# ATtinyBoard_capBall.net
KiCad netlist of a schematic drawn in EAGLE
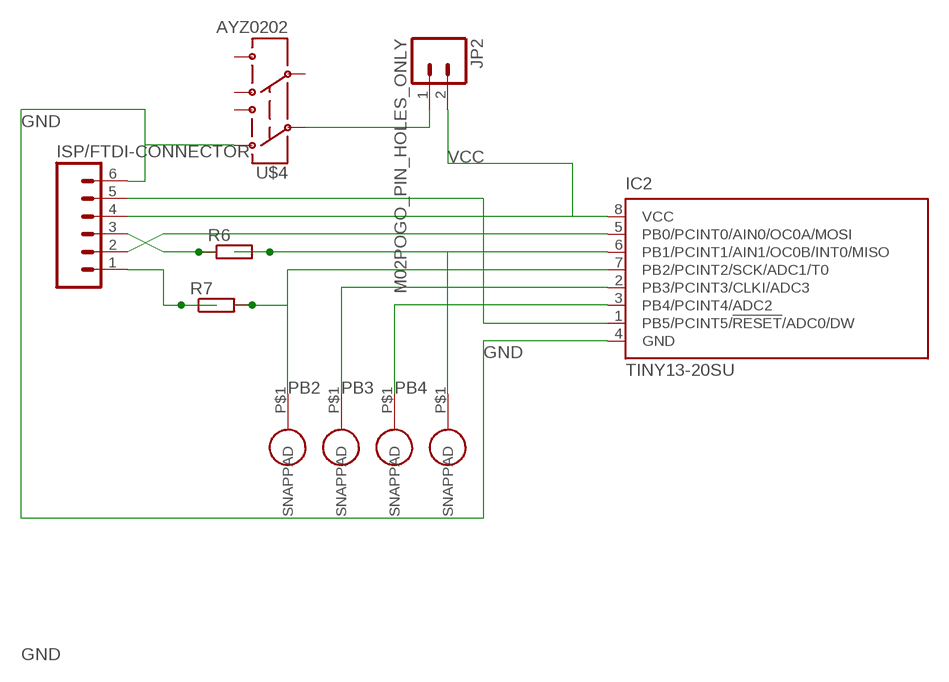
[diagram p0: schematic, sheet 1]

(export (version "E")
  (design (tool "Eeschema 10.0.6"))
  (components
    (comp (ref "IC2")
      (value "TINY13-20SU")
      (footprint "eagle-import:8S2")
      (fields (field (name "MPN") "ATTINY13-20SU"))
      (libsource (lib "eagle-import") (part "TINY13SU-20"))
    )
    (comp (ref "ISP/FTDI-CONNECTOR")
      (value "M06SMD")
      (footprint "eagle-import:1X06-SMD")
      (libsource (lib "eagle-import") (part "M06SMD"))
    )
    (comp (ref "JP2")
      (value "M02POGO_PIN_HOLES_ONLY")
      (footprint "eagle-import:1X02_PP_HOLES_ONLY")
      (libsource (lib "eagle-import") (part "M02POGO_PIN_HOLES_ONLY"))
    )
    (comp (ref "R6")
      (value "R-EU_R2012")
      (footprint "eagle-import:R2012")
      (libsource (lib "eagle-import") (part "R-EU_R2012"))
    )
    (comp (ref "R7")
      (value "R-EU_R2012")
      (footprint "eagle-import:R2012")
      (libsource (lib "eagle-import") (part "R-EU_R2012"))
    )
    (comp (ref "U$1")
      (value "SNAP-PAD_7MM_ROUND")
      (footprint "eagle-import:SNAP-PAD_7MM_RD")
      (libsource (lib "eagle-import") (part "SNAP-PAD_7MM_ROUND"))
    )
    (comp (ref "U$2")
      (value "SNAP-PAD_7MM_ROUND")
      (footprint "eagle-import:SNAP-PAD_7MM_RD")
      (libsource (lib "eagle-import") (part "SNAP-PAD_7MM_ROUND"))
    )
    (comp (ref "U$3")
      (value "SNAP-PAD_7MM_ROUND")
      (footprint "eagle-import:SNAP-PAD_7MM_RD")
      (libsource (lib "eagle-import") (part "SNAP-PAD_7MM_ROUND"))
    )
    (comp (ref "U$4")
      (value "AYZ0202")
      (footprint "eagle-import:AYZ0202")
      (libsource (lib "eagle-import") (part "AYZ0202"))
    )
    (comp (ref "U$6")
      (value "SNAP-PAD_7MM_ROUND")
      (footprint "eagle-import:SNAP-PAD_7MM_RD")
      (libsource (lib "eagle-import") (part "SNAP-PAD_7MM_ROUND"))
    )
  )
  (nets
    (net (code "1") (name "/GND") (class "Default")
      (node (ref "IC2") (pin "4") (pinfunction "GND_4") (pintype "power_in"))
      (node (ref "ISP/FTDI-CONNECTOR") (pin "6") (pinfunction "6_6") (pintype "passive"))
      (node (ref "U$4") (pin "3") (pinfunction "1_3") (pintype "bidirectional"))
    )
    (net (code "2") (name "/PB2") (class "Default")
      (node (ref "IC2") (pin "7") (pinfunction "PB2/PCINT2/SCK/ADC1/T0_7") (pintype "bidirectional"))
      (node (ref "R7") (pin "2") (pinfunction "2_2") (pintype "passive"))
      (node (ref "U$1") (pin "P$1") (pinfunction "SNAPPAD_P$1") (pintype "bidirectional"))
    )
    (net (code "3") (name "/PB3") (class "Default")
      (node (ref "IC2") (pin "2") (pinfunction "PB3/PCINT3/CLKI/ADC3_2") (pintype "bidirectional"))
      (node (ref "U$2") (pin "P$1") (pinfunction "SNAPPAD_P$1") (pintype "bidirectional"))
    )
    (net (code "4") (name "/PB4") (class "Default")
      (node (ref "IC2") (pin "3") (pinfunction "PB4/PCINT4/ADC2_3") (pintype "bidirectional"))
      (node (ref "U$3") (pin "P$1") (pinfunction "SNAPPAD_P$1") (pintype "bidirectional"))
    )
    (net (code "5") (name "/VCC") (class "Default")
      (node (ref "IC2") (pin "8") (pinfunction "VCC_8") (pintype "power_in"))
      (node (ref "ISP/FTDI-CONNECTOR") (pin "4") (pinfunction "4_4") (pintype "passive"))
      (node (ref "JP2") (pin "2") (pinfunction "2_2") (pintype "passive"))
    )
    (net (code "6") (name "Net-(IC2-PB0{slash}PCINT0{slash}AIN0{slash}OC0A{slash}MOSI)") (class "Default")
      (node (ref "IC2") (pin "5") (pinfunction "PB0/PCINT0/AIN0/OC0A/MOSI_5") (pintype "bidirectional"))
      (node (ref "ISP/FTDI-CONNECTOR") (pin "2") (pinfunction "2_2") (pintype "passive"))
    )
    (net (code "7") (name "Net-(IC2-PB1{slash}PCINT1{slash}AIN1{slash}OC0B{slash}INT0{slash}MISO)") (class "Default")
      (node (ref "IC2") (pin "6") (pinfunction "PB1/PCINT1/AIN1/OC0B/INT0/MISO_6") (pintype "bidirectional"))
      (node (ref "R6") (pin "2") (pinfunction "2_2") (pintype "passive"))
      (node (ref "U$6") (pin "P$1") (pinfunction "SNAPPAD_P$1") (pintype "bidirectional"))
    )
    (net (code "8") (name "Net-(IC2-PB5{slash}PCINT5{slash}~{RESET}{slash}ADC0{slash}DW)") (class "Default")
      (node (ref "IC2") (pin "1") (pinfunction "PB5/PCINT5/~{RESET}/ADC0/DW_1") (pintype "bidirectional"))
      (node (ref "ISP/FTDI-CONNECTOR") (pin "5") (pinfunction "5_5") (pintype "passive"))
    )
    (net (code "9") (name "Net-(ISP/FTDI-CONNECTOR-Pad1)") (class "Default")
      (node (ref "ISP/FTDI-CONNECTOR") (pin "1") (pinfunction "1_1") (pintype "passive"))
      (node (ref "R7") (pin "1") (pinfunction "1_1") (pintype "passive"))
    )
    (net (code "10") (name "Net-(ISP/FTDI-CONNECTOR-Pad3)") (class "Default")
      (node (ref "ISP/FTDI-CONNECTOR") (pin "3") (pinfunction "3_3") (pintype "passive"))
      (node (ref "R6") (pin "1") (pinfunction "1_1") (pintype "passive"))
    )
    (net (code "11") (name "Net-(JP2-Pad1)") (class "Default")
      (node (ref "JP2") (pin "1") (pinfunction "1_1") (pintype "passive"))
      (node (ref "U$4") (pin "2") (pinfunction "2_2") (pintype "bidirectional"))
    )
    (net (code "12") (name "unconnected-(U$4-3-Pad1)") (class "Default")
      (node (ref "U$4") (pin "1") (pinfunction "3_1") (pintype "bidirectional"))
    )
    (net (code "13") (name "unconnected-(U$4-4-Pad6)") (class "Default")
      (node (ref "U$4") (pin "6") (pinfunction "4_6") (pintype "bidirectional"))
    )
    (net (code "14") (name "unconnected-(U$4-6-Pad4)") (class "Default")
      (node (ref "U$4") (pin "4") (pinfunction "6_4") (pintype "bidirectional"))
    )
    (net (code "15") (name "unconnected-(U$4-Pad5)") (class "Default")
      (node (ref "U$4") (pin "5") (pinfunction "5_5") (pintype "bidirectional"))
    )
  )
)
